# Schematico_PCB.net
KiCad netlist of a schematic drawn in EAGLE
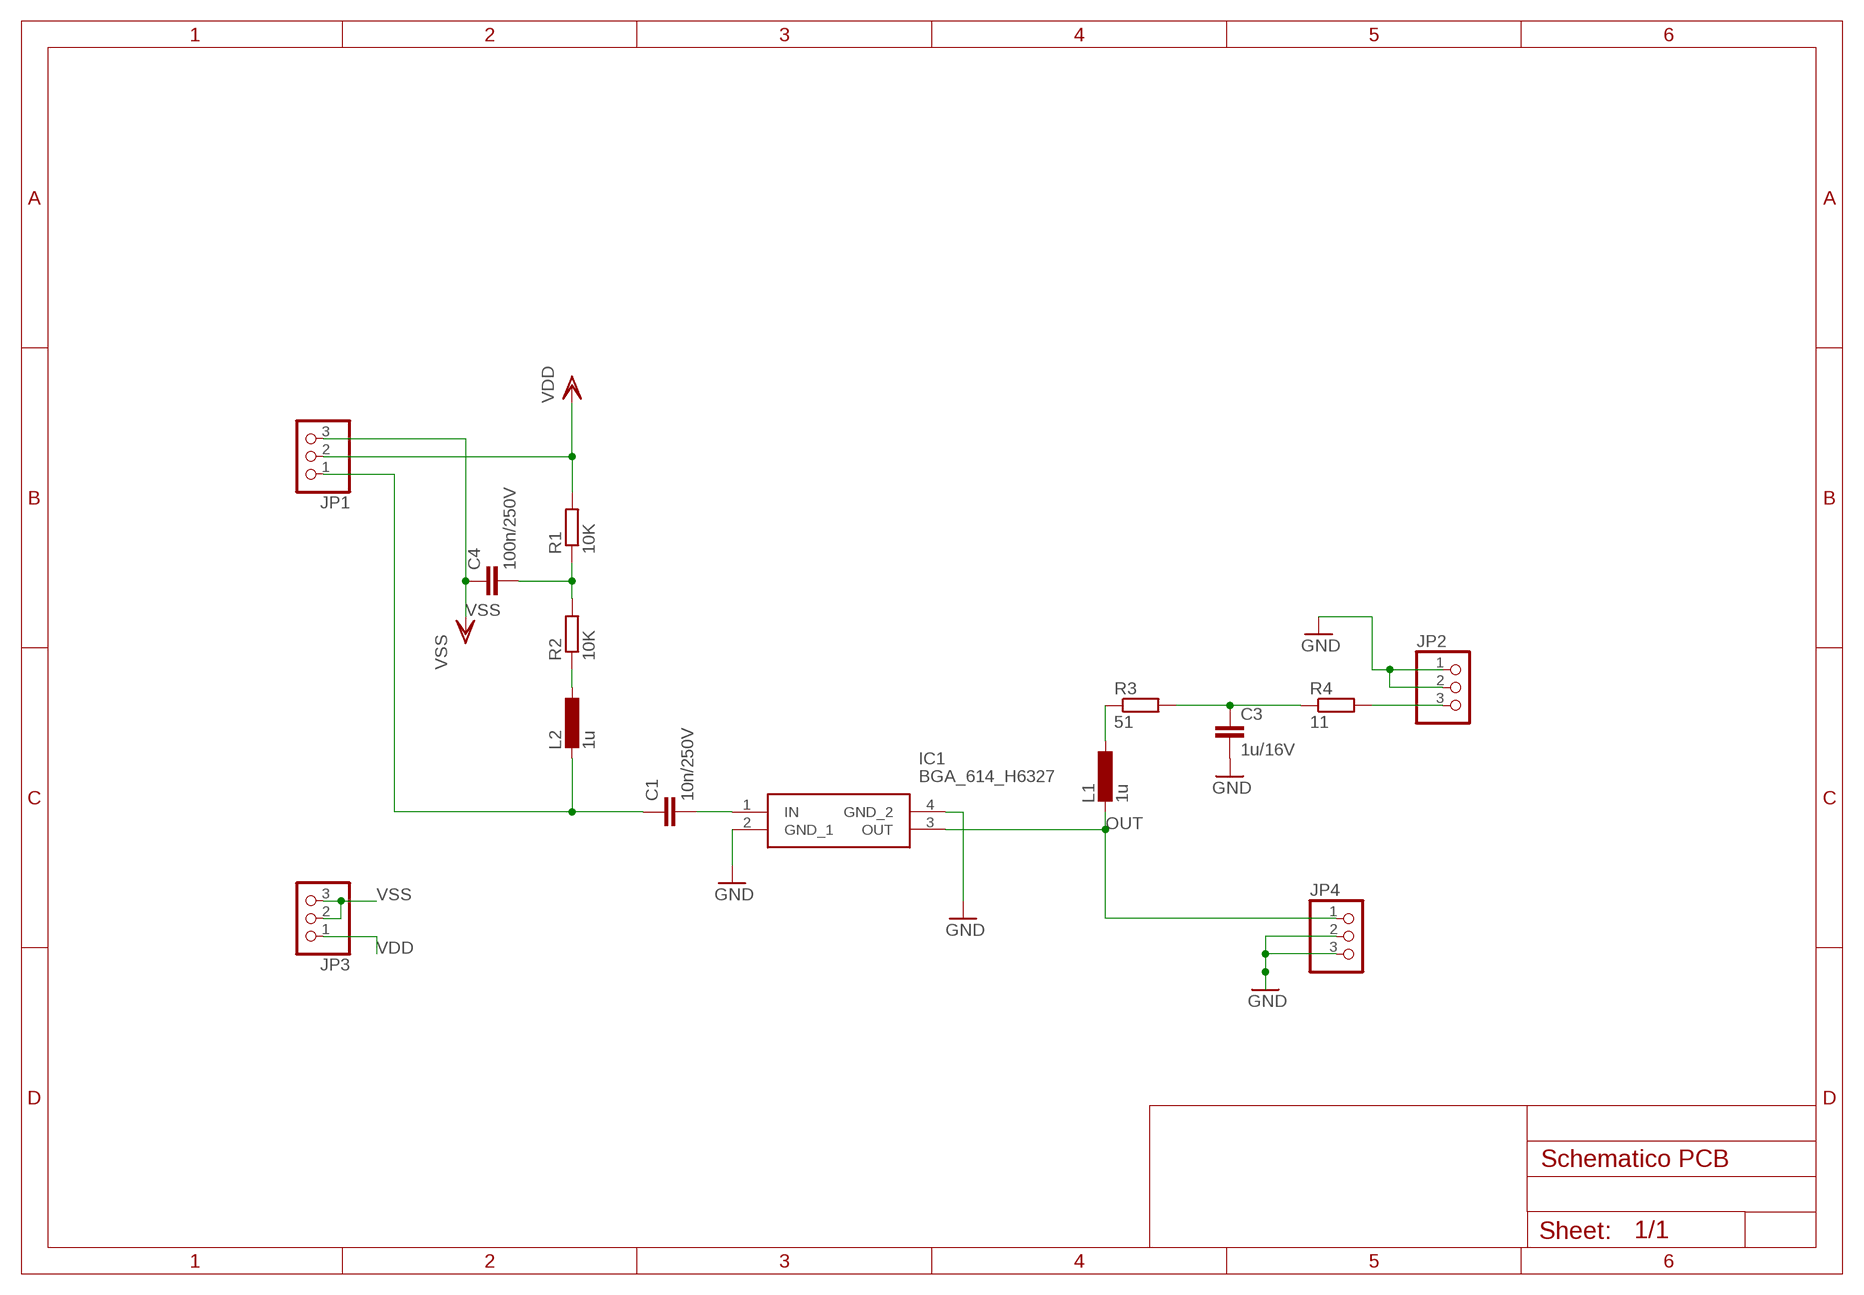
[diagram p0: schematic, sheet 1]

(export (version "E")
  (design (tool "Eeschema 10.0.6"))
  (components
    (comp (ref "C1")
      (value "10n/250V")
      (footprint "eagle-import:C0805")
      (libsource (lib "eagle-import") (part "C-EUC0805"))
    )
    (comp (ref "C3")
      (value "1u/16V")
      (footprint "eagle-import:C0805")
      (libsource (lib "eagle-import") (part "C-EUC0805"))
    )
    (comp (ref "C4")
      (value "100n/250V")
      (footprint "eagle-import:C0805")
      (libsource (lib "eagle-import") (part "C-EUC0805"))
    )
    (comp (ref "IC1")
      (value "BGA_614_H6327")
      (footprint "eagle-import:BGA614H6327")
      (fields
        (field (name "MANUFACTURER_PART_NUMBER") "BGA 614 H6327")
        (field (name "MOUSER_PART_NUMBER") "726-BGA614H6327XT")
      )
      (libsource (lib "eagle-import") (part "BGA_614_H6327"))
    )
    (comp (ref "JP1")
      (value "PINHD-1X3")
      (footprint "eagle-import:1X03")
      (libsource (lib "eagle-import") (part "PINHD-1X3"))
    )
    (comp (ref "JP2")
      (value "PINHD-1X3")
      (footprint "eagle-import:1X03")
      (libsource (lib "eagle-import") (part "PINHD-1X3"))
    )
    (comp (ref "JP3")
      (value "PINHD-1X3")
      (footprint "eagle-import:1X03")
      (libsource (lib "eagle-import") (part "PINHD-1X3"))
    )
    (comp (ref "JP4")
      (value "PINHD-1X3")
      (footprint "eagle-import:1X03")
      (libsource (lib "eagle-import") (part "PINHD-1X3"))
    )
    (comp (ref "L1")
      (value "1u")
      (footprint "eagle-import:L1812")
      (libsource (lib "eagle-import") (part "L-EUL1812"))
    )
    (comp (ref "L2")
      (value "1u")
      (footprint "eagle-import:L1812")
      (libsource (lib "eagle-import") (part "L-EUL1812"))
    )
    (comp (ref "R1")
      (value "10K")
      (footprint "eagle-import:R0805")
      (libsource (lib "eagle-import") (part "R-EU_R0805"))
    )
    (comp (ref "R2")
      (value "10K")
      (footprint "eagle-import:R0805")
      (libsource (lib "eagle-import") (part "R-EU_R0805"))
    )
    (comp (ref "R3")
      (value "51")
      (footprint "eagle-import:R0805")
      (libsource (lib "eagle-import") (part "R-EU_R0805"))
    )
    (comp (ref "R4")
      (value "11")
      (footprint "eagle-import:R0805")
      (libsource (lib "eagle-import") (part "R-EU_R0805"))
    )
  )
  (nets
    (net (code "1") (name "/OUT") (class "Default")
      (node (ref "IC1") (pin "3") (pinfunction "OUT_3") (pintype "bidirectional"))
      (node (ref "JP4") (pin "1") (pinfunction "1_1") (pintype "passive"))
      (node (ref "L1") (pin "2") (pinfunction "2_2") (pintype "passive"))
    )
    (net (code "2") (name "GND") (class "Default")
      (node (ref "C3") (pin "2") (pinfunction "2_2") (pintype "passive"))
      (node (ref "IC1") (pin "2") (pinfunction "GND_1_2") (pintype "bidirectional"))
      (node (ref "IC1") (pin "4") (pinfunction "GND_2_4") (pintype "bidirectional"))
      (node (ref "JP2") (pin "1") (pinfunction "1_1") (pintype "passive"))
      (node (ref "JP2") (pin "2") (pinfunction "2_2") (pintype "passive"))
      (node (ref "JP4") (pin "2") (pinfunction "2_2") (pintype "passive"))
      (node (ref "JP4") (pin "3") (pinfunction "3_3") (pintype "passive"))
    )
    (net (code "3") (name "Net-(C1-Pad1)") (class "Default")
      (node (ref "C1") (pin "1") (pinfunction "1_1") (pintype "passive"))
      (node (ref "JP1") (pin "1") (pinfunction "1_1") (pintype "passive"))
      (node (ref "L2") (pin "2") (pinfunction "2_2") (pintype "passive"))
    )
    (net (code "4") (name "Net-(C3-Pad1)") (class "Default")
      (node (ref "C3") (pin "1") (pinfunction "1_1") (pintype "passive"))
      (node (ref "R3") (pin "2") (pinfunction "2_2") (pintype "passive"))
      (node (ref "R4") (pin "1") (pinfunction "1_1") (pintype "passive"))
    )
    (net (code "5") (name "Net-(C4-Pad2)") (class "Default")
      (node (ref "C4") (pin "2") (pinfunction "2_2") (pintype "passive"))
      (node (ref "R1") (pin "1") (pinfunction "1_1") (pintype "passive"))
      (node (ref "R2") (pin "2") (pinfunction "2_2") (pintype "passive"))
    )
    (net (code "6") (name "Net-(IC1-IN)") (class "Default")
      (node (ref "C1") (pin "2") (pinfunction "2_2") (pintype "passive"))
      (node (ref "IC1") (pin "1") (pinfunction "IN_1") (pintype "bidirectional"))
    )
    (net (code "7") (name "Net-(JP2-Pad3)") (class "Default")
      (node (ref "JP2") (pin "3") (pinfunction "3_3") (pintype "passive"))
      (node (ref "R4") (pin "2") (pinfunction "2_2") (pintype "passive"))
    )
    (net (code "8") (name "Net-(L1-Pad1)") (class "Default")
      (node (ref "L1") (pin "1") (pinfunction "1_1") (pintype "passive"))
      (node (ref "R3") (pin "1") (pinfunction "1_1") (pintype "passive"))
    )
    (net (code "9") (name "Net-(L2-Pad1)") (class "Default")
      (node (ref "L2") (pin "1") (pinfunction "1_1") (pintype "passive"))
      (node (ref "R2") (pin "1") (pinfunction "1_1") (pintype "passive"))
    )
    (net (code "10") (name "VDD") (class "Default")
      (node (ref "JP1") (pin "2") (pinfunction "2_2") (pintype "passive"))
      (node (ref "JP3") (pin "1") (pinfunction "1_1") (pintype "passive"))
      (node (ref "R1") (pin "2") (pinfunction "2_2") (pintype "passive"))
    )
    (net (code "11") (name "VSS") (class "Default")
      (node (ref "C4") (pin "1") (pinfunction "1_1") (pintype "passive"))
      (node (ref "JP1") (pin "3") (pinfunction "3_3") (pintype "passive"))
      (node (ref "JP3") (pin "2") (pinfunction "2_2") (pintype "passive"))
      (node (ref "JP3") (pin "3") (pinfunction "3_3") (pintype "passive"))
    )
  )
)
